# YuanziSTM32.net
KiCad netlist of a schematic drawn in Altium Designer
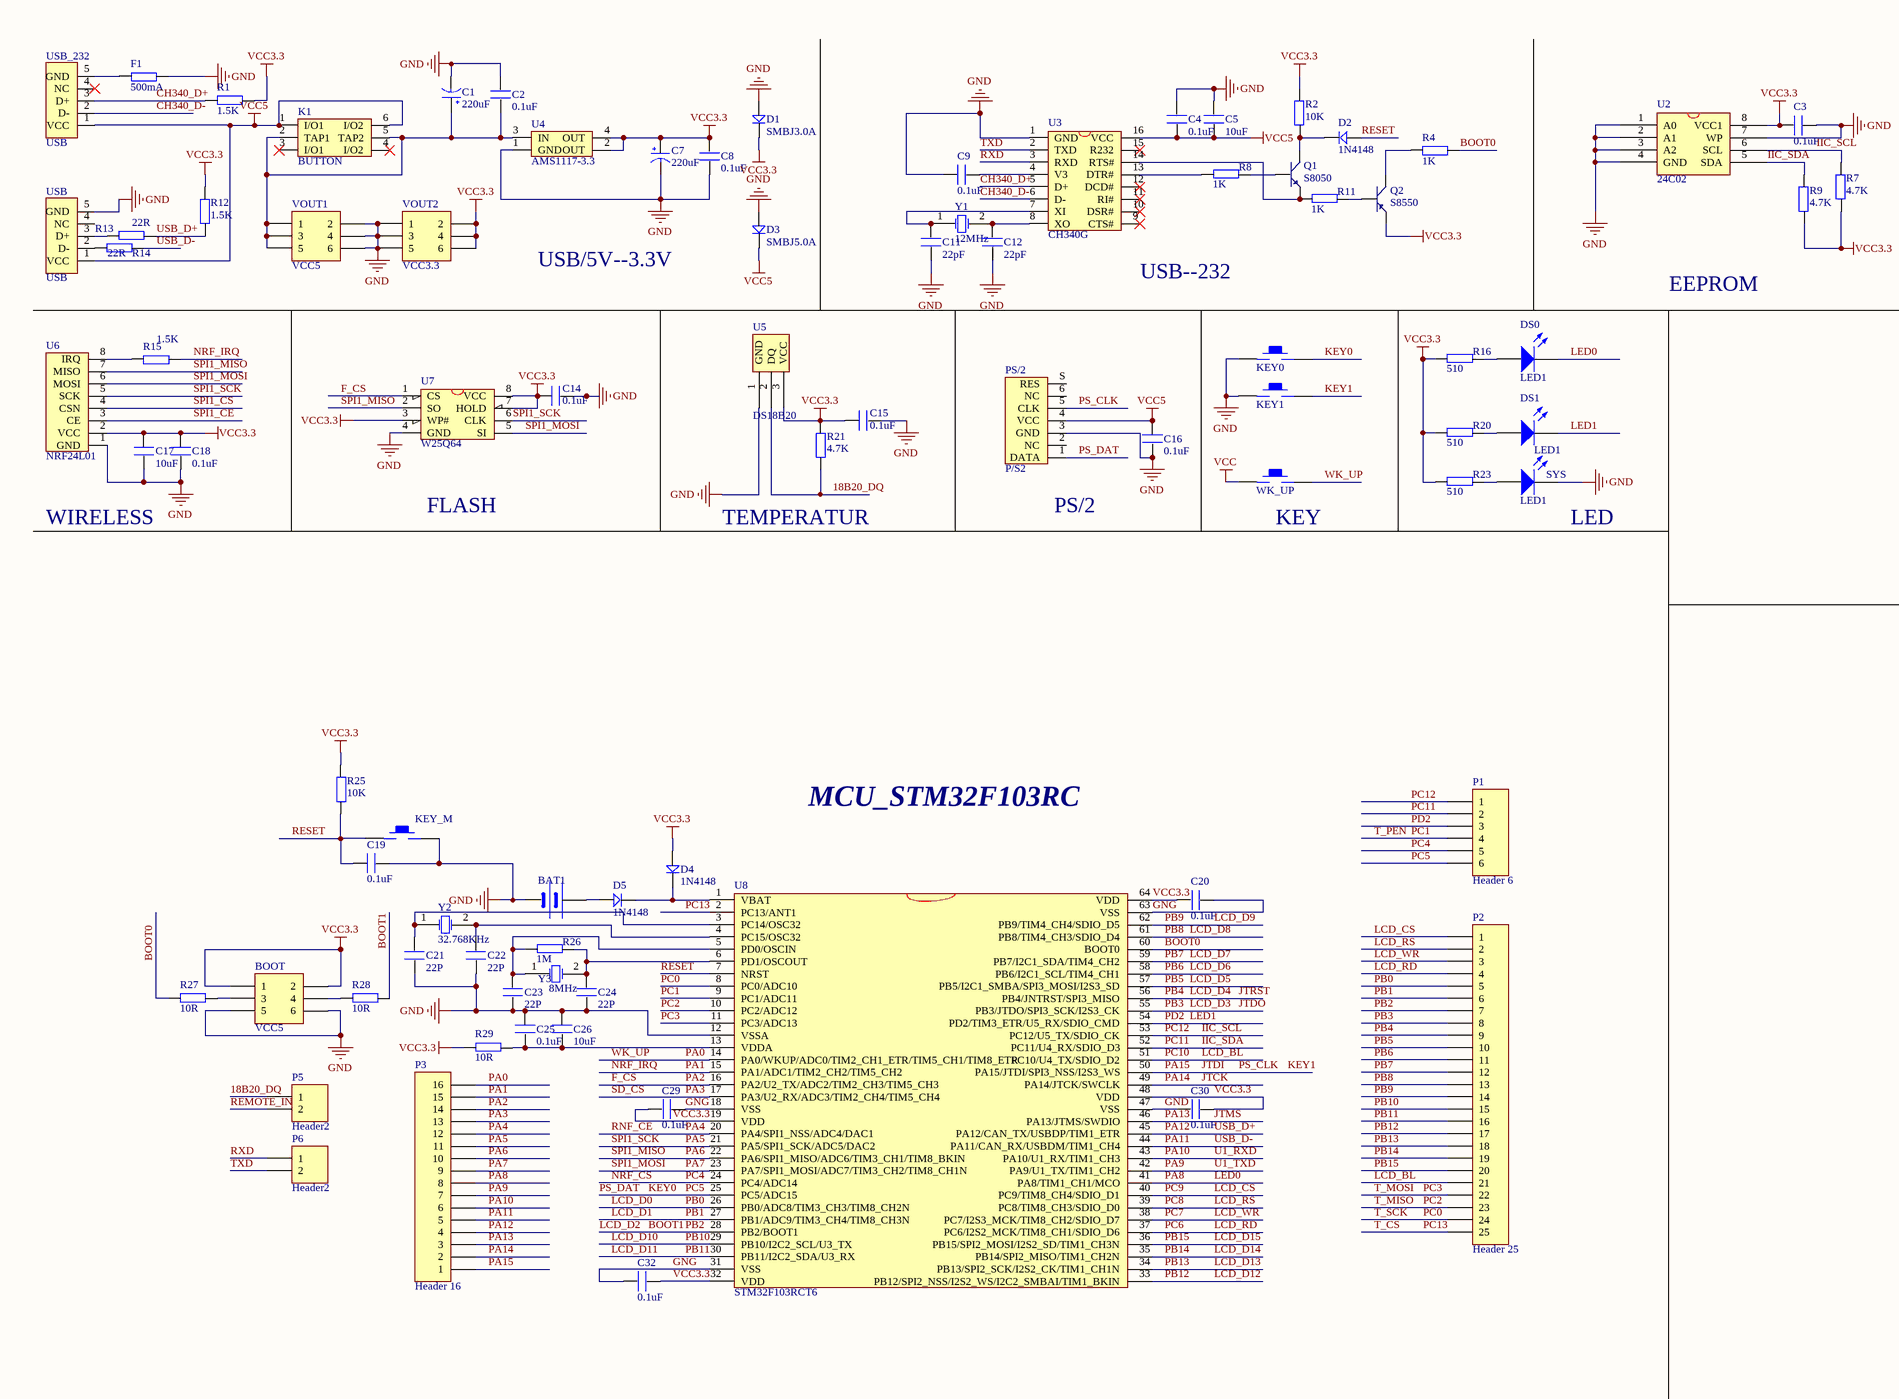
[diagram p0: YuanziSTM32.SchDoc, left]
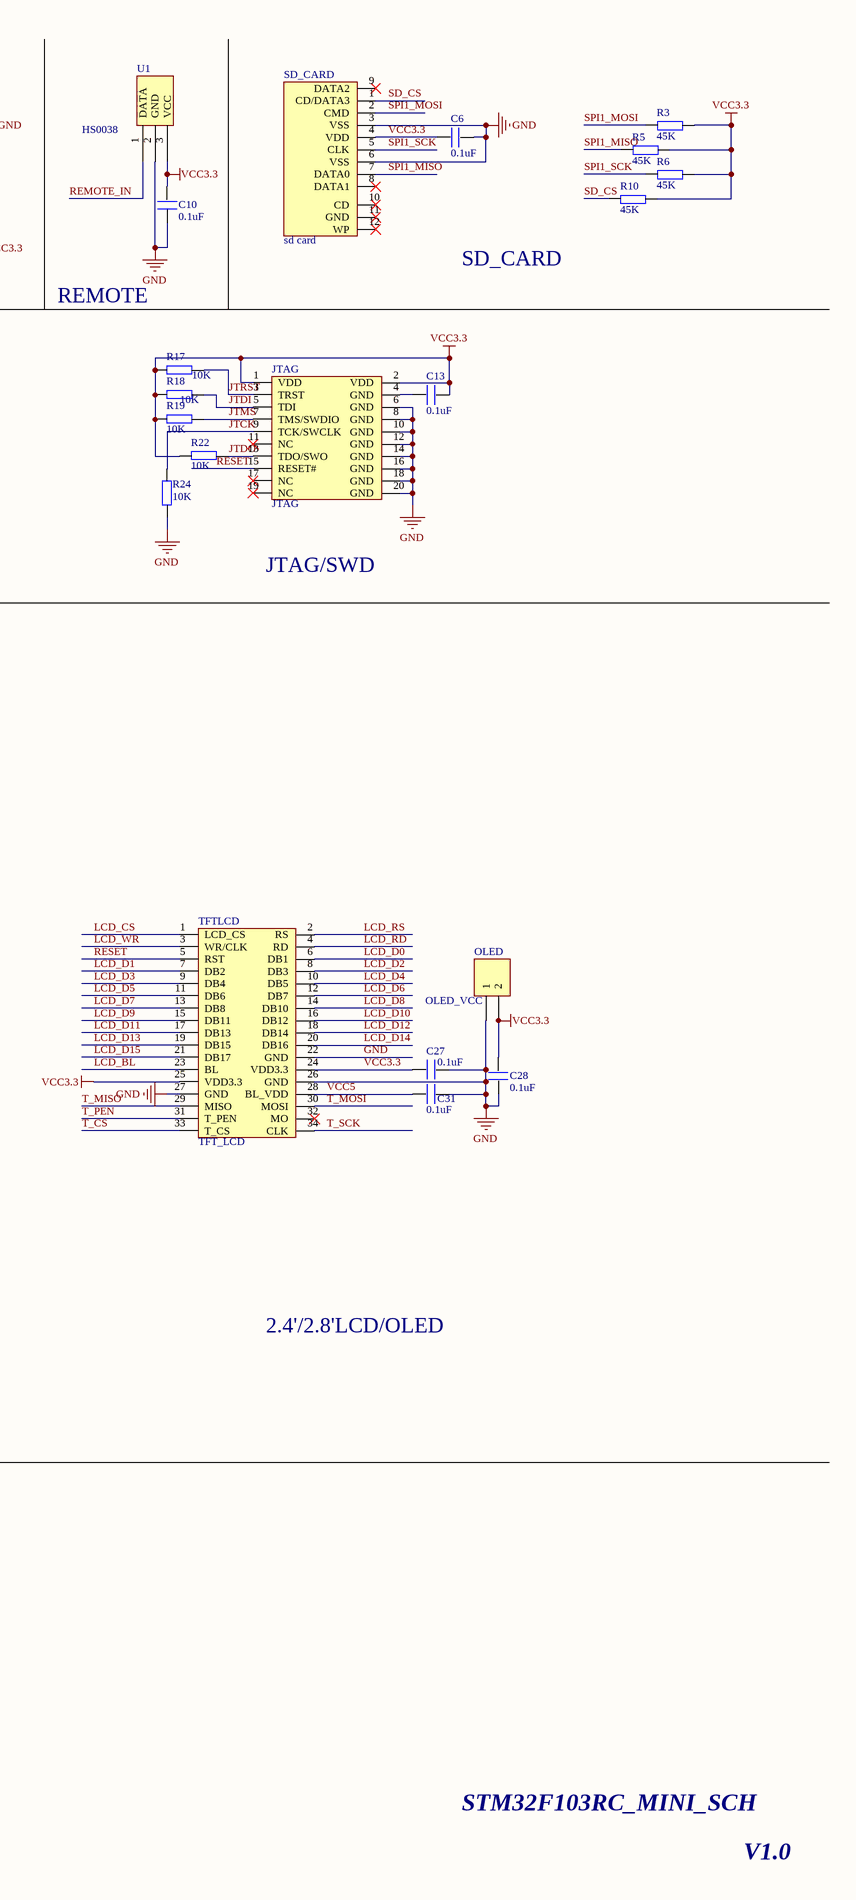
[diagram p1: YuanziSTM32.SchDoc, right]

(export (version "E")
  (design (tool "Eeschema 10.0.6"))
  (components
    (comp (ref "BAT1") (value "BATT") (footprint "BATTERY-CELL") (libsource (lib "CORE") (part "BAT")))
    (comp (ref "BOOT")
      (value "VCC5")
      (footprint "HDR2X3")
      (description "Header, 3-Pin, Dual row")
      (fields (field (name "PUBLISHER") "Altium Limited"))
      (libsource (lib "CORE") (part "Header 3X2"))
    )
    (comp (ref "C1") (value "220uF") (footprint "CC6.56.5") (libsource (lib "CORE") (part "CAP")))
    (comp (ref "C2") (value "0.1uF") (footprint "C0603") (libsource (lib "CORE") (part "C")))
    (comp (ref "C3") (value "0.1uF") (footprint "C0603") (libsource (lib "CORE") (part "C")))
    (comp (ref "C4") (value "0.1uF") (footprint "C0603") (libsource (lib "CORE") (part "C")))
    (comp (ref "C5") (value "10uF") (footprint "C0603") (libsource (lib "CORE") (part "C")))
    (comp (ref "C6") (value "0.1uF") (footprint "C0603") (libsource (lib "CORE") (part "C")))
    (comp (ref "C7") (value "220uF") (footprint "CC6.56.5") (libsource (lib "") (part "CAP_1")))
    (comp (ref "C8") (value "0.1uF") (footprint "C0603") (libsource (lib "CORE") (part "C")))
    (comp (ref "C9") (value "0.1uF") (footprint "C0603") (libsource (lib "CORE") (part "C")))
    (comp (ref "C10") (value "0.1uF") (footprint "C0603") (libsource (lib "CORE") (part "C")))
    (comp (ref "C11") (value "22pF") (footprint "C0603") (libsource (lib "CORE") (part "C")))
    (comp (ref "C12") (value "22pF") (footprint "C0603") (libsource (lib "CORE") (part "C")))
    (comp (ref "C13") (value "0.1uF") (footprint "C0603") (libsource (lib "CORE") (part "C")))
    (comp (ref "C14") (value "0.1uF") (footprint "C0603") (libsource (lib "CORE") (part "C")))
    (comp (ref "C15") (value "0.1uF") (footprint "C0603") (libsource (lib "CORE") (part "C")))
    (comp (ref "C16") (value "0.1uF") (footprint "C0603") (libsource (lib "CORE") (part "C")))
    (comp (ref "C17") (value "10uF") (footprint "C0603") (libsource (lib "CORE") (part "C")))
    (comp (ref "C18") (value "0.1uF") (footprint "C0603") (libsource (lib "CORE") (part "C")))
    (comp (ref "C19") (value "0.1uF") (footprint "C0603") (libsource (lib "CORE") (part "C")))
    (comp (ref "C20") (value "0.1uF") (footprint "C0603") (libsource (lib "CORE") (part "C")))
    (comp (ref "C21") (value "22P") (footprint "C0603") (libsource (lib "CORE") (part "C")))
    (comp (ref "C22") (value "22P") (footprint "C0603") (libsource (lib "CORE") (part "C")))
    (comp (ref "C23") (value "22P") (footprint "C0603") (libsource (lib "CORE") (part "C")))
    (comp (ref "C24") (value "22P") (footprint "C0603") (libsource (lib "CORE") (part "C")))
    (comp (ref "C25") (value "0.1uF") (footprint "C0603") (libsource (lib "CORE") (part "C")))
    (comp (ref "C26") (value "10uF") (footprint "C0603") (libsource (lib "CORE") (part "C")))
    (comp (ref "C27") (value "0.1uF") (footprint "C0603") (libsource (lib "CORE") (part "C")))
    (comp (ref "C28") (value "0.1uF") (footprint "C0603") (libsource (lib "CORE") (part "C")))
    (comp (ref "C29") (value "0.1uF") (footprint "C0603") (libsource (lib "CORE") (part "C")))
    (comp (ref "C30") (value "0.1uF") (footprint "C0603") (libsource (lib "CORE") (part "C")))
    (comp (ref "C31") (value "0.1uF") (footprint "C0603") (libsource (lib "CORE") (part "C")))
    (comp (ref "C32") (value "0.1uF") (footprint "C0603") (libsource (lib "CORE") (part "C")))
    (comp (ref "D1")
      (value "SMBJ3.0A")
      (footprint "DIODE_SOP")
      (description "1N4148")
      (libsource (lib "CORE") (part "D"))
    )
    (comp (ref "D2") (value "1N4148") (footprint "DIODE_SOP") (libsource (lib "CORE") (part "D")))
    (comp (ref "D3")
      (value "SMBJ5.0A")
      (footprint "DIODE_SOP")
      (description "1N4148")
      (libsource (lib "CORE") (part "D"))
    )
    (comp (ref "D4") (value "1N4148") (footprint "D0805") (libsource (lib "CORE") (part "D")))
    (comp (ref "D5") (value "1N4148") (footprint "D0805") (libsource (lib "CORE") (part "D")))
    (comp (ref "DS0")
      (value "LED1")
      (footprint "SMDLED")
      (description "Typical RED, GREEN, YELLOW, AMBER GaAs LED")
      (fields (field (name "PUBLISHER") "Altium Limited"))
      (libsource (lib "CORE") (part "LED2"))
    )
    (comp (ref "DS1")
      (value "LED1")
      (footprint "SMDLED")
      (description "Typical RED, GREEN, YELLOW, AMBER GaAs LED")
      (fields (field (name "PUBLISHER") "Altium Limited"))
      (libsource (lib "CORE") (part "LED2"))
    )
    (comp (ref "F1") (value "500mA") (footprint "0603P") (libsource (lib "CORE") (part "R")))
    (comp (ref "JTAG") (value "JTAG") (footprint "JTAG_20") (libsource (lib "CORE") (part "JTAG")))
    (comp (ref "K1") (value "BUTTON") (footprint "BTN8.5*8.5") (libsource (lib "CORE") (part "BUTTON")))
    (comp (ref "KEY0") (value "KEY_M") (footprint "SW-4PIN-DIP") (libsource (lib "CORE") (part "KEY_M")))
    (comp (ref "KEY1") (value "KEY_M") (footprint "SW-4PIN-DIP") (libsource (lib "CORE") (part "KEY_M")))
    (comp (ref "KEY_M") (value "KEY_M") (footprint "SW-4PIN-DIP") (libsource (lib "CORE") (part "KEY_M")))
    (comp (ref "OLED")
      (value "OLED_VCC")
      (footprint "HDR1X2")
      (description "Header, 2-Pin")
      (fields (field (name "PUBLISHER") "Altium Limited"))
      (libsource (lib "") (part "Header 2_1"))
    )
    (comp (ref "P1")
      (value "Header 6")
      (footprint "HDR1X6")
      (description "Header, 6-Pin")
      (fields (field (name "PUBLISHER") "Altium Limited"))
      (libsource (lib "CORE") (part "Header 6"))
    )
    (comp (ref "P2")
      (value "Header 25")
      (footprint "HDR1X25")
      (description "Header, 25-Pin")
      (fields (field (name "PUBLISHER") "Altium Limited"))
      (libsource (lib "CORE") (part "Header 25"))
    )
    (comp (ref "P3")
      (value "Header 16")
      (footprint "HDR1X16")
      (description "Header, 16-Pin")
      (fields (field (name "PUBLISHER") "Altium Limited"))
      (libsource (lib "CORE") (part "Header 16"))
    )
    (comp (ref "P5")
      (value "Header2")
      (footprint "HDR1X2")
      (description "Header, 2-Pin")
      (fields (field (name "PUBLISHER") "Altium Limited"))
      (libsource (lib "CORE") (part "Header 2"))
    )
    (comp (ref "P6")
      (value "Header2")
      (footprint "HDR1X2")
      (description "Header, 2-Pin")
      (fields (field (name "PUBLISHER") "Altium Limited"))
      (libsource (lib "CORE") (part "Header 2"))
    )
    (comp (ref "PS/2") (value "P/S2") (footprint "PS2-6PIN") (libsource (lib "CORE") (part "P/S2")))
    (comp (ref "Q1")
      (value "S8050")
      (footprint "SOT-23R")
      (description "8050/BCW846/BCW847")
      (libsource (lib "CORE") (part "NPN"))
    )
    (comp (ref "Q2")
      (value "S8550")
      (footprint "SOT-23R")
      (description "8550/BCW68")
      (libsource (lib "CORE") (part "PNP"))
    )
    (comp (ref "R1") (value "1.5K") (footprint "R0603") (libsource (lib "CORE") (part "R")))
    (comp (ref "R2") (value "10K") (footprint "R0603") (libsource (lib "CORE") (part "R")))
    (comp (ref "R3") (value "45K") (footprint "R0603") (libsource (lib "CORE") (part "R")))
    (comp (ref "R4") (value "1K") (footprint "R0603") (libsource (lib "CORE") (part "R")))
    (comp (ref "R5") (value "45K") (footprint "R0603") (libsource (lib "CORE") (part "R")))
    (comp (ref "R6") (value "45K") (footprint "R0603") (libsource (lib "CORE") (part "R")))
    (comp (ref "R7") (value "4.7K") (footprint "R0603") (libsource (lib "CORE") (part "R")))
    (comp (ref "R8") (value "1K") (footprint "R0603") (libsource (lib "CORE") (part "R")))
    (comp (ref "R9") (value "4.7K") (footprint "R0603") (libsource (lib "CORE") (part "R")))
    (comp (ref "R10") (value "45K") (footprint "R0603") (libsource (lib "CORE") (part "R")))
    (comp (ref "R11") (value "1K") (footprint "R0603") (libsource (lib "CORE") (part "R")))
    (comp (ref "R12") (value "1.5K") (footprint "R0603") (libsource (lib "CORE") (part "R")))
    (comp (ref "R13") (value "22R") (footprint "R0603") (libsource (lib "CORE") (part "R")))
    (comp (ref "R14") (value "22R") (footprint "R0603") (libsource (lib "CORE") (part "R")))
    (comp (ref "R15") (value "1.5K") (footprint "R0603") (libsource (lib "CORE") (part "R")))
    (comp (ref "R16") (value "510") (footprint "R0603") (libsource (lib "CORE") (part "R")))
    (comp (ref "R17") (value "10K") (footprint "R0603") (libsource (lib "CORE") (part "R")))
    (comp (ref "R18") (value "10K") (footprint "R0603") (libsource (lib "CORE") (part "R")))
    (comp (ref "R19") (value "10K") (footprint "R0603") (libsource (lib "CORE") (part "R")))
    (comp (ref "R20") (value "510") (footprint "R0603") (libsource (lib "CORE") (part "R")))
    (comp (ref "R21") (value "4.7K") (footprint "R0603") (libsource (lib "CORE") (part "R")))
    (comp (ref "R22") (value "10K") (footprint "R0603") (libsource (lib "CORE") (part "R")))
    (comp (ref "R23") (value "510") (footprint "R0603") (libsource (lib "CORE") (part "R")))
    (comp (ref "R24") (value "10K") (footprint "R0603") (libsource (lib "CORE") (part "R")))
    (comp (ref "R25") (value "10K") (footprint "R0603") (libsource (lib "CORE") (part "R")))
    (comp (ref "R26") (value "1M") (footprint "R0603") (libsource (lib "CORE") (part "R")))
    (comp (ref "R27") (value "10R") (footprint "R0603") (libsource (lib "CORE") (part "R")))
    (comp (ref "R28") (value "10R") (footprint "R0603") (libsource (lib "CORE") (part "R")))
    (comp (ref "R29") (value "10R") (footprint "R0603") (libsource (lib "CORE") (part "R")))
    (comp (ref "SD_CARD") (value "sd card") (footprint "SDCARD_L") (libsource (lib "CORE") (part "sd card")))
    (comp (ref "SYS")
      (value "LED1")
      (footprint "SMDLED")
      (description "Typical RED, GREEN, YELLOW, AMBER GaAs LED")
      (fields (field (name "PUBLISHER") "Altium Limited"))
      (libsource (lib "CORE") (part "LED2"))
    )
    (comp (ref "TFTLCD") (value "TFT_LCD") (footprint "DB2*17") (libsource (lib "CORE") (part "TFT_LCD")))
    (comp (ref "U1") (value "HS0038") (footprint "HS0038") (libsource (lib "CORE") (part "HS0038")))
    (comp (ref "U2") (value "24C02") (footprint "SOP-8") (libsource (lib "CORE") (part "24C256")))
    (comp (ref "U3")
      (value "CH340G")
      (footprint "SOIC16")
      (description "USB2UART")
      (libsource (lib "CORE") (part "CH340G"))
    )
    (comp (ref "U4") (value "AMS1117-3.3") (footprint "AMS1117") (libsource (lib "CORE") (part "AMS1117")))
    (comp (ref "U5") (value "DS18B20") (footprint "DS18B20") (libsource (lib "CORE") (part "DS18B20")))
    (comp (ref "U6") (value "NRF24L01") (footprint "NRF24L01") (libsource (lib "CORE") (part "NRF24L01")))
    (comp (ref "U7")
      (value "W25Q64")
      (footprint "SOP-8")
      (description "W25X16;SST25VF016;MX25L1605")
      (libsource (lib "CORE") (part "W25X16"))
    )
    (comp (ref "U8")
      (value "STM32F103RCT6")
      (footprint "LQFP64")
      (libsource (lib "CORE") (part "STM32F103RDT6"))
    )
    (comp (ref "USB") (value "USB") (footprint "USB/SM0.8-6H5") (libsource (lib "CORE") (part "USB5")))
    (comp (ref "USB_232") (value "USB") (footprint "USB/SM0.8-6H5") (libsource (lib "CORE") (part "USB5")))
    (comp (ref "VOUT1")
      (value "VCC5")
      (footprint "HDR2X3")
      (description "Header, 3-Pin, Dual row")
      (fields (field (name "PUBLISHER") "Altium Limited"))
      (libsource (lib "CORE") (part "Header 3X2"))
    )
    (comp (ref "VOUT2")
      (value "VCC3.3")
      (footprint "HDR2X3")
      (description "Header, 3-Pin, Dual row")
      (fields (field (name "PUBLISHER") "Altium Limited"))
      (libsource (lib "CORE") (part "Header 3X2"))
    )
    (comp (ref "WK_UP") (value "KEY_M") (footprint "SW-4PIN-DIP") (libsource (lib "CORE") (part "KEY_M")))
    (comp (ref "Y1")
      (value "12MHz")
      (footprint "XTAL")
      (description "Crystal Oscillator")
      (fields (field (name "PUBLISHER") "Altium Limited"))
      (libsource (lib "CORE") (part "XTAL"))
    )
    (comp (ref "Y2")
      (value "32.768KHz")
      (footprint "X_32.768KHZ - duplicate")
      (description "Crystal Oscillator")
      (fields (field (name "PUBLISHER") "Altium Limited"))
      (libsource (lib "CORE") (part "XTAL"))
    )
    (comp (ref "Y3")
      (value "8MHz")
      (footprint "XTAL")
      (description "Crystal Oscillator")
      (fields (field (name "PUBLISHER") "Altium Limited"))
      (libsource (lib "CORE") (part "XTAL"))
    )
  )
  (nets
    (net (code "1") (name "/18B20_DQ") (class "Default")
      (node (ref "P5") (pin "1") (pinfunction "1_1") (pintype "passive"))
      (node (ref "R21") (pin "1") (pintype "passive"))
      (node (ref "U5") (pin "2") (pinfunction "DQ_2") (pintype "passive"))
    )
    (net (code "2") (name "/BOOT0") (class "Default")
      (node (ref "R27") (pin "2") (pintype "passive"))
      (node (ref "R4") (pin "2") (pintype "passive"))
      (node (ref "U8") (pin "60") (pinfunction "BOOT0_60") (pintype "passive"))
    )
    (net (code "3") (name "/BOOT1") (class "Default")
      (node (ref "P2") (pin "7") (pinfunction "7_7") (pintype "passive"))
      (node (ref "R28") (pin "1") (pintype "passive"))
      (node (ref "TFTLCD") (pin "8") (pinfunction "DB3_8") (pintype "passive"))
      (node (ref "U8") (pin "28") (pinfunction "PB2/BOOT1_28") (pintype "passive"))
    )
    (net (code "4") (name "/CH340_D+") (class "Default")
      (node (ref "R1") (pin "2") (pintype "passive"))
      (node (ref "U3") (pin "5") (pinfunction "D+_5") (pintype "passive"))
      (node (ref "USB") (pin "3") (pinfunction "D+_3") (pintype "passive"))
    )
    (net (code "5") (name "/CH340_D-") (class "Default")
      (node (ref "U3") (pin "6") (pinfunction "D-_6") (pintype "passive"))
      (node (ref "USB") (pin "2") (pinfunction "D-_2") (pintype "passive"))
    )
    (net (code "6") (name "/F_CS") (class "Default")
      (node (ref "P3") (pin "14") (pinfunction "14_14") (pintype "passive"))
      (node (ref "U7") (pin "1") (pinfunction "CS_1") (pintype "passive"))
      (node (ref "U8") (pin "16") (pinfunction "PA2/U2_TX/ADC2/TIM2_CH3/TIM5_CH3_16") (pintype "passive"))
    )
    (net (code "7") (name "/GNG") (class "Default")
      (node (ref "C20") (pin "1") (pintype "passive"))
      (node (ref "C29") (pin "1") (pintype "passive"))
      (node (ref "C32") (pin "2") (pintype "passive"))
      (node (ref "U8") (pin "18") (pinfunction "VSS_18") (pintype "passive"))
      (node (ref "U8") (pin "31") (pinfunction "VSS_31") (pintype "passive"))
      (node (ref "U8") (pin "63") (pinfunction "VSS_63") (pintype "passive"))
    )
    (net (code "8") (name "/IIC_SCL") (class "Default")
      (node (ref "P1") (pin "1") (pinfunction "1_1") (pintype "passive"))
      (node (ref "R7") (pin "1") (pintype "passive"))
      (node (ref "U2") (pin "6") (pinfunction "SCL_6") (pintype "passive"))
      (node (ref "U8") (pin "53") (pinfunction "PC12/U5_TX/SDIO_CK_53") (pintype "passive"))
    )
    (net (code "9") (name "/IIC_SDA") (class "Default")
      (node (ref "P1") (pin "2") (pinfunction "2_2") (pintype "passive"))
      (node (ref "R9") (pin "1") (pintype "passive"))
      (node (ref "U2") (pin "5") (pinfunction "SDA_5") (pintype "passive"))
      (node (ref "U8") (pin "52") (pinfunction "PC11/U4_RX/SDIO_D3_52") (pintype "passive"))
    )
    (net (code "10") (name "/JTCK") (class "Default")
      (node (ref "JTAG") (pin "9") (pinfunction "TCK/SWCLK_9") (pintype "passive"))
      (node (ref "P3") (pin "2") (pinfunction "2_2") (pintype "passive"))
      (node (ref "R24") (pin "1") (pintype "passive"))
      (node (ref "U8") (pin "49") (pinfunction "PA14/JTCK/SWCLK_49") (pintype "passive"))
    )
    (net (code "11") (name "/JTDI") (class "Default")
      (node (ref "JTAG") (pin "5") (pinfunction "TDI_5") (pintype "passive"))
      (node (ref "KEY1") (pin "2") (pinfunction "2_2") (pintype "passive"))
      (node (ref "P3") (pin "1") (pinfunction "1_1") (pintype "passive"))
      (node (ref "PS/2") (pin "5") (pinfunction "CLK_5") (pintype "passive"))
      (node (ref "R18") (pin "1") (pintype "passive"))
      (node (ref "U8") (pin "50") (pinfunction "PA15/JTDI/SPI3_NSS/I2S3_WS_50") (pintype "passive"))
    )
    (net (code "12") (name "/JTDO") (class "Default")
      (node (ref "JTAG") (pin "13") (pinfunction "TDO/SWO_13") (pintype "passive"))
      (node (ref "P2") (pin "8") (pinfunction "8_8") (pintype "passive"))
      (node (ref "R22") (pin "1") (pintype "passive"))
      (node (ref "TFTLCD") (pin "9") (pinfunction "DB4_9") (pintype "passive"))
      (node (ref "U8") (pin "55") (pinfunction "PB3/JTDO/SPI3_SCK/I2S3_CK_55") (pintype "passive"))
    )
    (net (code "13") (name "/JTMS") (class "Default")
      (node (ref "JTAG") (pin "7") (pinfunction "TMS/SWDIO_7") (pintype "passive"))
      (node (ref "P3") (pin "3") (pinfunction "3_3") (pintype "passive"))
      (node (ref "R19") (pin "1") (pintype "passive"))
      (node (ref "U8") (pin "46") (pinfunction "PA13/JTMS/SWDIO_46") (pintype "passive"))
    )
    (net (code "14") (name "/JTRST") (class "Default")
      (node (ref "JTAG") (pin "3") (pinfunction "TRST_3") (pintype "passive"))
      (node (ref "P2") (pin "9") (pinfunction "9_9") (pintype "passive"))
      (node (ref "R17") (pin "1") (pintype "passive"))
      (node (ref "TFTLCD") (pin "10") (pinfunction "DB5_10") (pintype "passive"))
      (node (ref "U8") (pin "56") (pinfunction "PB4/JNTRST/SPI3_MISO_56") (pintype "passive"))
    )
    (net (code "15") (name "/KEY0") (class "Default")
      (node (ref "KEY0") (pin "2") (pinfunction "2_2") (pintype "passive"))
      (node (ref "P1") (pin "6") (pinfunction "6_6") (pintype "passive"))
      (node (ref "PS/2") (pin "1") (pinfunction "DATA_1") (pintype "passive"))
      (node (ref "U8") (pin "25") (pinfunction "PC5/ADC15_25") (pintype "passive"))
    )
    (net (code "16") (name "/LCD_BL") (class "Default")
      (node (ref "P2") (pin "21") (pinfunction "21_21") (pintype "passive"))
      (node (ref "TFTLCD") (pin "23") (pinfunction "BL_23") (pintype "passive"))
      (node (ref "U8") (pin "51") (pinfunction "PC10/U4_TX/SDIO_D2_51") (pintype "passive"))
    )
    (net (code "17") (name "/LCD_CS") (class "Default")
      (node (ref "P2") (pin "1") (pinfunction "1_1") (pintype "passive"))
      (node (ref "TFTLCD") (pin "1") (pinfunction "LCD_CS_1") (pintype "passive"))
      (node (ref "U8") (pin "40") (pinfunction "PC9/TIM8_CH4/SDIO_D1_40") (pintype "passive"))
    )
    (net (code "18") (name "/LCD_D0") (class "Default")
      (node (ref "P2") (pin "5") (pinfunction "5_5") (pintype "passive"))
      (node (ref "TFTLCD") (pin "6") (pinfunction "DB1_6") (pintype "passive"))
      (node (ref "U8") (pin "26") (pinfunction "PB0/ADC8/TIM3_CH3/TIM8_CH2N_26") (pintype "passive"))
    )
    (net (code "19") (name "/LCD_D1") (class "Default")
      (node (ref "P2") (pin "6") (pinfunction "6_6") (pintype "passive"))
      (node (ref "TFTLCD") (pin "7") (pinfunction "DB2_7") (pintype "passive"))
      (node (ref "U8") (pin "27") (pinfunction "PB1/ADC9/TIM3_CH4/TIM8_CH3N_27") (pintype "passive"))
    )
    (net (code "20") (name "/LCD_D5") (class "Default")
      (node (ref "P2") (pin "10") (pinfunction "10_10") (pintype "passive"))
      (node (ref "TFTLCD") (pin "11") (pinfunction "DB6_11") (pintype "passive"))
      (node (ref "U8") (pin "57") (pinfunction "PB5/I2C1_SMBA/SPI3_MOSI/I2S3_SD_57") (pintype "passive"))
    )
    (net (code "21") (name "/LCD_D6") (class "Default")
      (node (ref "P2") (pin "11") (pinfunction "11_11") (pintype "passive"))
      (node (ref "TFTLCD") (pin "12") (pinfunction "DB7_12") (pintype "passive"))
      (node (ref "U8") (pin "58") (pinfunction "PB6/I2C1_SCL/TIM4_CH1_58") (pintype "passive"))
    )
    (net (code "22") (name "/LCD_D7") (class "Default")
      (node (ref "P2") (pin "12") (pinfunction "12_12") (pintype "passive"))
      (node (ref "TFTLCD") (pin "13") (pinfunction "DB8_13") (pintype "passive"))
      (node (ref "U8") (pin "59") (pinfunction "PB7/I2C1_SDA/TIM4_CH2_59") (pintype "passive"))
    )
    (net (code "23") (name "/LCD_D8") (class "Default")
      (node (ref "P2") (pin "13") (pinfunction "13_13") (pintype "passive"))
      (node (ref "TFTLCD") (pin "14") (pinfunction "DB10_14") (pintype "passive"))
      (node (ref "U8") (pin "61") (pinfunction "PB8/TIM4_CH3/SDIO_D4_61") (pintype "passive"))
    )
    (net (code "24") (name "/LCD_D9") (class "Default")
      (node (ref "P2") (pin "14") (pinfunction "14_14") (pintype "passive"))
      (node (ref "TFTLCD") (pin "15") (pinfunction "DB11_15") (pintype "passive"))
      (node (ref "U8") (pin "62") (pinfunction "PB9/TIM4_CH4/SDIO_D5_62") (pintype "passive"))
    )
    (net (code "25") (name "/LCD_D10") (class "Default")
      (node (ref "P2") (pin "15") (pinfunction "15_15") (pintype "passive"))
      (node (ref "TFTLCD") (pin "16") (pinfunction "DB12_16") (pintype "passive"))
      (node (ref "U8") (pin "29") (pinfunction "PB10/I2C2_SCL/U3_TX_29") (pintype "passive"))
    )
    (net (code "26") (name "/LCD_D11") (class "Default")
      (node (ref "P2") (pin "16") (pinfunction "16_16") (pintype "passive"))
      (node (ref "TFTLCD") (pin "17") (pinfunction "DB13_17") (pintype "passive"))
      (node (ref "U8") (pin "30") (pinfunction "PB11/I2C2_SDA/U3_RX_30") (pintype "passive"))
    )
    (net (code "27") (name "/LCD_D12") (class "Default")
      (node (ref "P2") (pin "17") (pinfunction "17_17") (pintype "passive"))
      (node (ref "TFTLCD") (pin "18") (pinfunction "DB14_18") (pintype "passive"))
      (node (ref "U8") (pin "33") (pinfunction "PB12/SPI2_NSS/I2S2_WS/I2C2_SMBAI/TIM1_BKIN_33") (pintype "passive"))
    )
    (net (code "28") (name "/LCD_D13") (class "Default")
      (node (ref "P2") (pin "18") (pinfunction "18_18") (pintype "passive"))
      (node (ref "TFTLCD") (pin "19") (pinfunction "DB15_19") (pintype "passive"))
      (node (ref "U8") (pin "34") (pinfunction "PB13/SPI2_SCK/I2S2_CK/TIM1_CH1N_34") (pintype "passive"))
    )
    (net (code "29") (name "/LCD_D14") (class "Default")
      (node (ref "P2") (pin "19") (pinfunction "19_19") (pintype "passive"))
      (node (ref "TFTLCD") (pin "20") (pinfunction "DB16_20") (pintype "passive"))
      (node (ref "U8") (pin "35") (pinfunction "PB14/SPI2_MISO/TIM1_CH2N_35") (pintype "passive"))
    )
    (net (code "30") (name "/LCD_D15") (class "Default")
      (node (ref "P2") (pin "20") (pinfunction "20_20") (pintype "passive"))
      (node (ref "TFTLCD") (pin "21") (pinfunction "DB17_21") (pintype "passive"))
      (node (ref "U8") (pin "36") (pinfunction "PB15/SPI2_MOSI/I2S2_SD/TIM1_CH3N_36") (pintype "passive"))
    )
    (net (code "31") (name "/LCD_RD") (class "Default")
      (node (ref "P2") (pin "4") (pinfunction "4_4") (pintype "passive"))
      (node (ref "TFTLCD") (pin "4") (pinfunction "RD_4") (pintype "passive"))
      (node (ref "U8") (pin "37") (pinfunction "PC6/I2S2_MCK/TIM8_CH1/SDIO_D6_37") (pintype "passive"))
    )
    (net (code "32") (name "/LCD_RS") (class "Default")
      (node (ref "P2") (pin "2") (pinfunction "2_2") (pintype "passive"))
      (node (ref "TFTLCD") (pin "2") (pinfunction "RS_2") (pintype "passive"))
      (node (ref "U8") (pin "39") (pinfunction "PC8/TIM8_CH3/SDIO_D0_39") (pintype "passive"))
    )
    (net (code "33") (name "/LCD_WR") (class "Default")
      (node (ref "P2") (pin "3") (pinfunction "3_3") (pintype "passive"))
      (node (ref "TFTLCD") (pin "3") (pinfunction "WR/CLK_3") (pintype "passive"))
      (node (ref "U8") (pin "38") (pinfunction "PC7/I2S3_MCK/TIM8_CH2/SDIO_D7_38") (pintype "passive"))
    )
    (net (code "34") (name "/LED0") (class "Default")
      (node (ref "DS0") (pin "2") (pinfunction "K_2") (pintype "passive"))
      (node (ref "P3") (pin "8") (pinfunction "8_8") (pintype "passive"))
      (node (ref "U8") (pin "41") (pinfunction "PA8/TIM1_CH1/MCO_41") (pintype "passive"))
    )
    (net (code "35") (name "/LED1") (class "Default")
      (node (ref "DS1") (pin "2") (pinfunction "K_2") (pintype "passive"))
      (node (ref "P1") (pin "3") (pinfunction "3_3") (pintype "passive"))
      (node (ref "U8") (pin "54") (pinfunction "PD2/TIM3_ETR/U5_RX/SDIO_CMD_54") (pintype "passive"))
    )
    (net (code "36") (name "/NRF_CS") (class "Default")
      (node (ref "P1") (pin "5") (pinfunction "5_5") (pintype "passive"))
      (node (ref "U8") (pin "24") (pinfunction "PC4/ADC14_24") (pintype "passive"))
    )
    (net (code "37") (name "/NRF_IRQ") (class "Default")
      (node (ref "P3") (pin "15") (pinfunction "15_15") (pintype "passive"))
      (node (ref "R15") (pin "2") (pintype "passive"))
      (node (ref "U8") (pin "15") (pinfunction "PA1/ADC1/TIM2_CH2/TIM5_CH2_15") (pintype "passive"))
    )
    (net (code "38") (name "/PA0") (class "Default")
      (node (ref "P3") (pin "16") (pinfunction "16_16") (pintype "passive"))
      (node (ref "U8") (pin "14") (pinfunction "PA0/WKUP/ADC0/TIM2_CH1_ETR/TIM5_CH1/TIM8_ETR_14") (pintype "passive"))
      (node (ref "WK_UP") (pin "2") (pinfunction "2_2") (pintype "passive"))
    )
    (net (code "39") (name "/PA3") (class "Default")
      (node (ref "P3") (pin "13") (pinfunction "13_13") (pintype "passive"))
      (node (ref "R10") (pin "1") (pintype "passive"))
      (node (ref "SD_CARD") (pin "1") (pinfunction "CD/DATA3_1") (pintype "passive"))
      (node (ref "U8") (pin "17") (pinfunction "PA3/U2_RX/ADC3/TIM2_CH4/TIM5_CH4_17") (pintype "passive"))
    )
    (net (code "40") (name "/PA4") (class "Default")
      (node (ref "P3") (pin "12") (pinfunction "12_12") (pintype "passive"))
      (node (ref "U8") (pin "20") (pinfunction "PA4/SPI1_NSS/ADC4/DAC1_20") (pintype "passive"))
    )
    (net (code "41") (name "/PA5") (class "Default")
      (node (ref "P3") (pin "11") (pinfunction "11_11") (pintype "passive"))
      (node (ref "R6") (pin "1") (pintype "passive"))
      (node (ref "SD_CARD") (pin "5") (pinfunction "CLK_5") (pintype "passive"))
      (node (ref "U6") (pin "5") (pinfunction "SCK_5") (pintype "passive"))
      (node (ref "U7") (pin "6") (pinfunction "CLK_6") (pintype "passive"))
      (node (ref "U8") (pin "21") (pinfunction "PA5/SPI1_SCK/ADC5/DAC2_21") (pintype "passive"))
    )
    (net (code "42") (name "/PA6") (class "Default")
      (node (ref "P3") (pin "10") (pinfunction "10_10") (pintype "passive"))
      (node (ref "R5") (pin "1") (pintype "passive"))
      (node (ref "SD_CARD") (pin "7") (pinfunction "DATA0_7") (pintype "passive"))
      (node (ref "U6") (pin "7") (pinfunction "MISO_7") (pintype "passive"))
      (node (ref "U7") (pin "2") (pinfunction "SO_2") (pintype "passive"))
      (node (ref "U8") (pin "22") (pinfunction "PA6/SPI1_MISO/ADC6/TIM3_CH1/TIM8_BKIN_22") (pintype "passive"))
    )
    (net (code "43") (name "/PA7") (class "Default")
      (node (ref "P3") (pin "9") (pinfunction "9_9") (pintype "passive"))
      (node (ref "R3") (pin "1") (pintype "passive"))
      (node (ref "SD_CARD") (pin "2") (pinfunction "CMD_2") (pintype "passive"))
      (node (ref "U6") (pin "6") (pinfunction "MOSI_6") (pintype "passive"))
      (node (ref "U7") (pin "5") (pinfunction "SI_5") (pintype "passive"))
      (node (ref "U8") (pin "23") (pinfunction "PA7/SPI1_MOSI/ADC7/TIM3_CH2/TIM8_CH1N_23") (pintype "passive"))
    )
    (net (code "44") (name "/PA9") (class "Default")
      (node (ref "P3") (pin "7") (pinfunction "7_7") (pintype "passive"))
      (node (ref "U8") (pin "42") (pinfunction "PA9/U1_TX/TIM1_CH2_42") (pintype "passive"))
    )
    (net (code "45") (name "/PA10") (class "Default")
      (node (ref "P3") (pin "6") (pinfunction "6_6") (pintype "passive"))
      (node (ref "U8") (pin "43") (pinfunction "PA10/U1_RX/TIM1_CH3_43") (pintype "passive"))
    )
    (net (code "46") (name "/PA11") (class "Default")
      (node (ref "P3") (pin "5") (pinfunction "5_5") (pintype "passive"))
      (node (ref "R14") (pin "1") (pintype "passive"))
      (node (ref "U8") (pin "44") (pinfunction "PA11/CAN_RX/USBDM/TIM1_CH4_44") (pintype "passive"))
    )
    (net (code "47") (name "/PA12") (class "Default")
      (node (ref "P3") (pin "4") (pinfunction "4_4") (pintype "passive"))
      (node (ref "R12") (pin "2") (pintype "passive"))
      (node (ref "R13") (pin "1") (pintype "passive"))
      (node (ref "U8") (pin "45") (pinfunction "PA12/CAN_TX/USBDP/TIM1_ETR_45") (pintype "passive"))
    )
    (net (code "48") (name "/PC0") (class "Default")
      (node (ref "P2") (pin "24") (pinfunction "24_24") (pintype "passive"))
      (node (ref "TFTLCD") (pin "34") (pinfunction "CLK_34") (pintype "passive"))
      (node (ref "U8") (pin "8") (pinfunction "PC0/ADC10_8") (pintype "passive"))
    )
    (net (code "49") (name "/PC1") (class "Default")
      (node (ref "P1") (pin "4") (pinfunction "4_4") (pintype "passive"))
      (node (ref "TFTLCD") (pin "31") (pinfunction "T_PEN_31") (pintype "passive"))
      (node (ref "U8") (pin "9") (pinfunction "PC1/ADC11_9") (pintype "passive"))
    )
    (net (code "50") (name "/PC2") (class "Default")
      (node (ref "P2") (pin "23") (pinfunction "23_23") (pintype "passive"))
      (node (ref "TFTLCD") (pin "29") (pinfunction "MISO_29") (pintype "passive"))
      (node (ref "U8") (pin "10") (pinfunction "PC2/ADC12_10") (pintype "passive"))
    )
    (net (code "51") (name "/PC3") (class "Default")
      (node (ref "P2") (pin "22") (pinfunction "22_22") (pintype "passive"))
      (node (ref "TFTLCD") (pin "30") (pinfunction "MOSI_30") (pintype "passive"))
      (node (ref "U8") (pin "11") (pinfunction "PC3/ADC13_11") (pintype "passive"))
    )
    (net (code "52") (name "/PC13") (class "Default")
      (node (ref "P2") (pin "25") (pinfunction "25_25") (pintype "passive"))
      (node (ref "TFTLCD") (pin "33") (pinfunction "T_CS_33") (pintype "passive"))
      (node (ref "U8") (pin "2") (pinfunction "PC13/ANT1_2") (pintype "passive"))
    )
    (net (code "53") (name "/REMOTE_IN") (class "Default")
      (node (ref "P5") (pin "2") (pinfunction "2_2") (pintype "passive"))
      (node (ref "U1") (pin "1") (pinfunction "DATA_1") (pintype "passive"))
    )
    (net (code "54") (name "/RESET") (class "Default")
      (node (ref "C19") (pin "1") (pintype "passive"))
      (node (ref "D2") (pin "1") (pintype "passive"))
      (node (ref "JTAG") (pin "15") (pinfunction "RESET#_15") (pintype "passive"))
      (node (ref "KEY_M") (pin "1") (pinfunction "1_1") (pintype "passive"))
      (node (ref "R25") (pin "1") (pintype "passive"))
      (node (ref "TFTLCD") (pin "5") (pinfunction "RST_5") (pintype "passive"))
      (node (ref "U8") (pin "7") (pinfunction "NRST_7") (pintype "passive"))
    )
    (net (code "55") (name "/RXD") (class "Default")
      (node (ref "P6") (pin "1") (pinfunction "1_1") (pintype "passive"))
      (node (ref "U3") (pin "3") (pinfunction "RXD_3") (pintype "passive"))
    )
    (net (code "56") (name "/SPI1_CE") (class "Default")
      (node (ref "U6") (pin "3") (pinfunction "CE_3") (pintype "passive"))
    )
    (net (code "57") (name "/SPI1_CS") (class "Default")
      (node (ref "U6") (pin "4") (pinfunction "CSN_4") (pintype "passive"))
    )
    (net (code "58") (name "/TXD") (class "Default")
      (node (ref "P6") (pin "2") (pinfunction "2_2") (pintype "passive"))
      (node (ref "U3") (pin "2") (pinfunction "TXD_2") (pintype "passive"))
    )
    (net (code "59") (name "GND") (class "Default")
      (node (ref "BAT1") (pin "2") (pinfunction "GND_2") (pintype "passive"))
      (node (ref "BOOT") (pin "5") (pinfunction "5_5") (pintype "passive"))
      (node (ref "BOOT") (pin "6") (pinfunction "6_6") (pintype "passive"))
      (node (ref "C1") (pin "2") (pinfunction "GND_2") (pintype "passive"))
      (node (ref "C10") (pin "2") (pintype "passive"))
      (node (ref "C11") (pin "1") (pintype "passive"))
      (node (ref "C12") (pin "1") (pintype "passive"))
      (node (ref "C14") (pin "2") (pintype "passive"))
      (node (ref "C15") (pin "2") (pintype "passive"))
      (node (ref "C16") (pin "1") (pintype "passive"))
      (node (ref "C17") (pin "1") (pintype "passive"))
      (node (ref "C18") (pin "1") (pintype "passive"))
      (node (ref "C19") (pin "2") (pintype "passive"))
      (node (ref "C2") (pin "2") (pintype "passive"))
      (node (ref "C21") (pin "1") (pintype "passive"))
      (node (ref "C22") (pin "1") (pintype "passive"))
      (node (ref "C23") (pin "1") (pintype "passive"))
      (node (ref "C24") (pin "1") (pintype "passive"))
      (node (ref "C25") (pin "2") (pintype "passive"))
      (node (ref "C26") (pin "2") (pintype "passive"))
      (node (ref "C27") (pin "1") (pintype "passive"))
      (node (ref "C28") (pin "2") (pintype "passive"))
      (node (ref "C3") (pin "1") (pintype "passive"))
      (node (ref "C30") (pin "2") (pintype "passive"))
      (node (ref "C31") (pin "1") (pintype "passive"))
      (node (ref "C4") (pin "2") (pintype "passive"))
      (node (ref "C5") (pin "2") (pintype "passive"))
      (node (ref "C6") (pin "2") (pintype "passive"))
      (node (ref "C7") (pin "2") (pinfunction "GND_2") (pintype "passive"))
      (node (ref "C8") (pin "2") (pintype "passive"))
      (node (ref "C9") (pin "1") (pintype "passive"))
      (node (ref "D1") (pin "1") (pintype "passive"))
      (node (ref "D3") (pin "1") (pintype "passive"))
      (node (ref "F1") (pin "2") (pintype "passive"))
      (node (ref "JTAG") (pin "10") (pinfunction "GND_10") (pintype "passive"))
      (node (ref "JTAG") (pin "12") (pinfunction "GND_12") (pintype "passive"))
      (node (ref "JTAG") (pin "14") (pinfunction "GND_14") (pintype "passive"))
      (node (ref "JTAG") (pin "16") (pinfunction "GND_16") (pintype "passive"))
      (node (ref "JTAG") (pin "18") (pinfunction "GND_18") (pintype "passive"))
      (node (ref "JTAG") (pin "20") (pinfunction "GND_20") (pintype "passive"))
      (node (ref "JTAG") (pin "6") (pinfunction "GND_6") (pintype "passive"))
      (node (ref "JTAG") (pin "8") (pinfunction "GND_8") (pintype "passive"))
      (node (ref "KEY0") (pin "1") (pinfunction "1_1") (pintype "passive"))
      (node (ref "KEY1") (pin "1") (pinfunction "1_1") (pintype "passive"))
      (node (ref "KEY_M") (pin "2") (pinfunction "2_2") (pintype "passive"))
      (node (ref "OLED") (pin "1") (pinfunction "1_1") (pintype "passive"))
      (node (ref "PS/2") (pin "3") (pinfunction "GND_3") (pintype "passive"))
      (node (ref "R24") (pin "2") (pintype "passive"))
      (node (ref "SD_CARD") (pin "3") (pinfunction "VSS_3") (pintype "passive"))
      (node (ref "SD_CARD") (pin "6") (pinfunction "VSS_6") (pintype "passive"))
      (node (ref "SYS") (pin "2") (pinfunction "K_2") (pintype "passive"))
      (node (ref "TFTLCD") (pin "22") (pinfunction "GND_22") (pintype "passive"))
      (node (ref "TFTLCD") (pin "26") (pinfunction "GND_26") (pintype "passive"))
      (node (ref "TFTLCD") (pin "27") (pinfunction "GND_27") (pintype "passive"))
      (node (ref "U1") (pin "2") (pinfunction "GND_2") (pintype "passive"))
      (node (ref "U2") (pin "1") (pinfunction "A0_1") (pintype "passive"))
      (node (ref "U2") (pin "2") (pinfunction "A1_2") (pintype "passive"))
      (node (ref "U2") (pin "3") (pinfunction "A2_3") (pintype "passive"))
      (node (ref "U2") (pin "4") (pinfunction "GND_4") (pintype "passive"))
      (node (ref "U2") (pin "7") (pinfunction "WP_7") (pintype "passive"))
      (node (ref "U3") (pin "1") (pinfunction "GND_1") (pintype "passive"))
      (node (ref "U4") (pin "1") (pinfunction "GND_1") (pintype "passive"))
      (node (ref "U5") (pin "1") (pinfunction "GND_1") (pintype "passive"))
      (node (ref "U6") (pin "1") (pinfunction "GND_1") (pintype "passive"))
      (node (ref "U7") (pin "4") (pinfunction "GND_4") (pintype "passive"))
      (node (ref "U8") (pin "12") (pinfunction "VSSA_12") (pintype "passive"))
      (node (ref "U8") (pin "47") (pinfunction "VSS_47") (pintype "passive"))
      (node (ref "USB_232") (pin "5") (pinfunction "GND_5") (pintype "passive"))
      (node (ref "VOUT1") (pin "2") (pinfunction "2_2") (pintype "passive"))
      (node (ref "VOUT1") (pin "4") (pinfunction "4_4") (pintype "passive"))
      (node (ref "VOUT1") (pin "6") (pinfunction "6_6") (pintype "passive"))
      (node (ref "VOUT2") (pin "1") (pinfunction "1_1") (pintype "passive"))
      (node (ref "VOUT2") (pin "3") (pinfunction "3_3") (pintype "passive"))
      (node (ref "VOUT2") (pin "5") (pinfunction "5_5") (pintype "passive"))
    )
    (net (code "60") (name "Net-(BAT1-VCC)") (class "Default")
      (node (ref "BAT1") (pin "1") (pinfunction "VCC_1") (pintype "passive"))
      (node (ref "D5") (pin "1") (pintype "passive"))
    )
    (net (code "61") (name "Net-(BOOT-Pad3)") (class "Default")
      (node (ref "BOOT") (pin "3") (pinfunction "3_3") (pintype "passive"))
      (node (ref "R27") (pin "1") (pintype "passive"))
    )
    (net (code "62") (name "Net-(BOOT-Pad4)") (class "Default")
      (node (ref "BOOT") (pin "4") (pinfunction "4_4") (pintype "passive"))
      (node (ref "R28") (pin "2") (pintype "passive"))
    )
    (net (code "63") (name "Net-(C1-VCC)") (class "Default")
      (node (ref "C1") (pin "1") (pinfunction "VCC_1") (pintype "passive"))
      (node (ref "C2") (pin "1") (pintype "passive"))
      (node (ref "K1") (pin "2") (pinfunction "TAP1_2") (pintype "passive"))
      (node (ref "K1") (pin "5") (pinfunction "TAP2_5") (pintype "passive"))
      (node (ref "U4") (pin "3") (pinfunction "IN_3") (pintype "passive"))
      (node (ref "VOUT1") (pin "1") (pinfunction "1_1") (pintype "passive"))
      (node (ref "VOUT1") (pin "3") (pinfunction "3_3") (pintype "passive"))
      (node (ref "VOUT1") (pin "5") (pinfunction "5_5") (pintype "passive"))
    )
    (net (code "64") (name "Net-(C13-Pad2)") (class "Default")
      (node (ref "C13") (pin "2") (pintype "passive"))
      (node (ref "JTAG") (pin "4") (pinfunction "GND_4") (pintype "passive"))
    )
    (net (code "65") (name "Net-(DS0-A)") (class "Default")
      (node (ref "DS0") (pin "1") (pinfunction "A_1") (pintype "passive"))
      (node (ref "R16") (pin "1") (pintype "passive"))
    )
    (net (code "66") (name "Net-(DS1-A)") (class "Default")
      (node (ref "DS1") (pin "1") (pinfunction "A_1") (pintype "passive"))
      (node (ref "R20") (pin "1") (pintype "passive"))
    )
    (net (code "67") (name "Net-(Q1-B)") (class "Default")
      (node (ref "Q1") (pin "2") (pinfunction "B_2") (pintype "passive"))
      (node (ref "R8") (pin "1") (pintype "passive"))
    )
    (net (code "68") (name "Net-(Q1-C)") (class "Default")
      (node (ref "D2") (pin "2") (pintype "passive"))
      (node (ref "Q1") (pin "3") (pinfunction "C_3") (pintype "passive"))
      (node (ref "R2") (pin "2") (pintype "passive"))
    )
    (net (code "69") (name "Net-(Q1-E)") (class "Default")
      (node (ref "Q1") (pin "1") (pinfunction "E_1") (pintype "passive"))
      (node (ref "R11") (pin "2") (pintype "passive"))
      (node (ref "U3") (pin "14") (pinfunction "RTS#_14") (pintype "passive"))
    )
    (net (code "70") (name "Net-(Q2-B)") (class "Default")
      (node (ref "Q2") (pin "2") (pinfunction "B_2") (pintype "passive"))
      (node (ref "R11") (pin "1") (pintype "passive"))
    )
    (net (code "71") (name "Net-(Q2-C)") (class "Default")
      (node (ref "Q2") (pin "3") (pinfunction "C_3") (pintype "passive"))
      (node (ref "R4") (pin "1") (pintype "passive"))
    )
    (net (code "72") (name "Net-(SYS-A)") (class "Default")
      (node (ref "R23") (pin "1") (pintype "passive"))
      (node (ref "SYS") (pin "1") (pinfunction "A_1") (pintype "passive"))
    )
    (net (code "73") (name "Net-(U3-DTR#)") (class "Default")
      (node (ref "R8") (pin "2") (pintype "passive"))
      (node (ref "U3") (pin "13") (pinfunction "DTR#_13") (pintype "passive"))
    )
    (net (code "74") (name "Net-(U3-V3)") (class "Default")
      (node (ref "C9") (pin "2") (pintype "passive"))
      (node (ref "U3") (pin "4") (pinfunction "V3_4") (pintype "passive"))
    )
    (net (code "75") (name "Net-(U3-XI)") (class "Default")
      (node (ref "C11") (pin "2") (pintype "passive"))
      (node (ref "U3") (pin "7") (pinfunction "XI_7") (pintype "passive"))
      (node (ref "Y1") (pin "1") (pinfunction "OSC1_1") (pintype "passive"))
    )
    (net (code "76") (name "Net-(U3-XO)") (class "Default")
      (node (ref "C12") (pin "2") (pintype "passive"))
      (node (ref "U3") (pin "8") (pinfunction "XO_8") (pintype "passive"))
      (node (ref "Y1") (pin "2") (pinfunction "OSC2_2") (pintype "passive"))
    )
    (net (code "77") (name "Net-(U6-IRQ)") (class "Default")
      (node (ref "R15") (pin "1") (pintype "passive"))
      (node (ref "U6") (pin "8") (pinfunction "IRQ_8") (pintype "passive"))
    )
    (net (code "78") (name "Net-(U8-PC14{slash}OSC32)") (class "Default")
      (node (ref "C21") (pin "2") (pintype "passive"))
      (node (ref "U8") (pin "3") (pinfunction "PC14/OSC32_3") (pintype "passive"))
      (node (ref "Y2") (pin "1") (pinfunction "OSC1_1") (pintype "passive"))
    )
    (net (code "79") (name "Net-(U8-PC15{slash}OSC32)") (class "Default")
      (node (ref "C22") (pin "2") (pintype "passive"))
      (node (ref "U8") (pin "4") (pinfunction "PC15/OSC32_4") (pintype "passive"))
      (node (ref "Y2") (pin "2") (pinfunction "OSC2_2") (pintype "passive"))
    )
    (net (code "80") (name "Net-(U8-PD0{slash}OSCIN)") (class "Default")
      (node (ref "C23") (pin "2") (pintype "passive"))
      (node (ref "R26") (pin "2") (pintype "passive"))
      (node (ref "U8") (pin "5") (pinfunction "PD0/OSCIN_5") (pintype "passive"))
      (node (ref "Y3") (pin "1") (pinfunction "OSC1_1") (pintype "passive"))
    )
    (net (code "81") (name "Net-(U8-PD1{slash}OSCOUT)") (class "Default")
      (node (ref "C24") (pin "2") (pintype "passive"))
      (node (ref "R26") (pin "1") (pintype "passive"))
      (node (ref "U8") (pin "6") (pinfunction "PD1/OSCOUT_6") (pintype "passive"))
      (node (ref "Y3") (pin "2") (pinfunction "OSC2_2") (pintype "passive"))
    )
    (net (code "82") (name "Net-(U8-VBAT)") (class "Default")
      (node (ref "D4") (pin "2") (pintype "passive"))
      (node (ref "D5") (pin "2") (pintype "passive"))
      (node (ref "U8") (pin "1") (pinfunction "VBAT_1") (pintype "passive"))
    )
    (net (code "83") (name "Net-(U8-VDDA)") (class "Default")
      (node (ref "C25") (pin "1") (pintype "passive"))
      (node (ref "C26") (pin "1") (pintype "passive"))
      (node (ref "R29") (pin "1") (pintype "passive"))
      (node (ref "U8") (pin "13") (pinfunction "VDDA_13") (pintype "passive"))
    )
    (net (code "84") (name "Net-(USB-GND)") (class "Default")
      (node (ref "F1") (pin "1") (pintype "passive"))
      (node (ref "USB") (pin "5") (pinfunction "GND_5") (pintype "passive"))
    )
    (net (code "85") (name "Net-(USB_232-D+)") (class "Default")
      (node (ref "R13") (pin "2") (pintype "passive"))
      (node (ref "USB_232") (pin "3") (pinfunction "D+_3") (pintype "passive"))
    )
    (net (code "86") (name "Net-(USB_232-D-)") (class "Default")
      (node (ref "R14") (pin "2") (pintype "passive"))
      (node (ref "USB_232") (pin "2") (pinfunction "D-_2") (pintype "passive"))
    )
    (net (code "87") (name "VCC") (class "Default")
      (node (ref "WK_UP") (pin "1") (pinfunction "1_1") (pintype "passive"))
    )
    (net (code "88") (name "VCC3.3") (class "Default")
      (node (ref "BOOT") (pin "1") (pinfunction "1_1") (pintype "passive"))
      (node (ref "BOOT") (pin "2") (pinfunction "2_2") (pintype "passive"))
      (node (ref "C10") (pin "1") (pintype "passive"))
      (node (ref "C13") (pin "1") (pintype "passive"))
      (node (ref "C14") (pin "1") (pintype "passive"))
      (node (ref "C15") (pin "1") (pintype "passive"))
      (node (ref "C17") (pin "2") (pintype "passive"))
      (node (ref "C18") (pin "2") (pintype "passive"))
      (node (ref "C20") (pin "2") (pintype "passive"))
      (node (ref "C27") (pin "2") (pintype "passive"))
      (node (ref "C28") (pin "1") (pintype "passive"))
      (node (ref "C29") (pin "2") (pintype "passive"))
      (node (ref "C3") (pin "2") (pintype "passive"))
      (node (ref "C30") (pin "1") (pintype "passive"))
      (node (ref "C32") (pin "1") (pintype "passive"))
      (node (ref "C6") (pin "1") (pintype "passive"))
      (node (ref "C7") (pin "1") (pinfunction "VCC_1") (pintype "passive"))
      (node (ref "C8") (pin "1") (pintype "passive"))
      (node (ref "D1") (pin "2") (pintype "passive"))
      (node (ref "D4") (pin "1") (pintype "passive"))
      (node (ref "JTAG") (pin "1") (pinfunction "VDD_1") (pintype "passive"))
      (node (ref "JTAG") (pin "2") (pinfunction "VDD_2") (pintype "passive"))
      (node (ref "OLED") (pin "2") (pinfunction "2_2") (pintype "passive"))
      (node (ref "Q2") (pin "1") (pinfunction "E_1") (pintype "passive"))
      (node (ref "R1") (pin "1") (pintype "passive"))
      (node (ref "R10") (pin "2") (pintype "passive"))
      (node (ref "R12") (pin "1") (pintype "passive"))
      (node (ref "R16") (pin "2") (pintype "passive"))
      (node (ref "R17") (pin "2") (pintype "passive"))
      (node (ref "R18") (pin "2") (pintype "passive"))
      (node (ref "R19") (pin "2") (pintype "passive"))
      (node (ref "R2") (pin "1") (pintype "passive"))
      (node (ref "R20") (pin "2") (pintype "passive"))
      (node (ref "R21") (pin "2") (pintype "passive"))
      (node (ref "R22") (pin "2") (pintype "passive"))
      (node (ref "R23") (pin "2") (pintype "passive"))
      (node (ref "R25") (pin "2") (pintype "passive"))
      (node (ref "R29") (pin "2") (pintype "passive"))
      (node (ref "R3") (pin "2") (pintype "passive"))
      (node (ref "R5") (pin "2") (pintype "passive"))
      (node (ref "R6") (pin "2") (pintype "passive"))
      (node (ref "R7") (pin "2") (pintype "passive"))
      (node (ref "R9") (pin "2") (pintype "passive"))
      (node (ref "SD_CARD") (pin "4") (pinfunction "VDD_4") (pintype "passive"))
      (node (ref "TFTLCD") (pin "24") (pinfunction "VDD3.3_24") (pintype "passive"))
      (node (ref "TFTLCD") (pin "25") (pinfunction "VDD3.3_25") (pintype "passive"))
      (node (ref "U1") (pin "3") (pinfunction "VCC_3") (pintype "passive"))
      (node (ref "U2") (pin "8") (pinfunction "VCC1_8") (pintype "passive"))
      (node (ref "U4") (pin "2") (pinfunction "OUT_2") (pintype "passive"))
      (node (ref "U4") (pin "4") (pinfunction "OUT_4") (pintype "passive"))
      (node (ref "U5") (pin "3") (pinfunction "VCC_3") (pintype "passive"))
      (node (ref "U6") (pin "2") (pinfunction "VCC_2") (pintype "passive"))
      (node (ref "U7") (pin "3") (pinfunction "WP#_3") (pintype "passive"))
      (node (ref "U7") (pin "7") (pinfunction "HOLD_7") (pintype "passive"))
      (node (ref "U7") (pin "8") (pinfunction "VCC_8") (pintype "passive"))
      (node (ref "U8") (pin "19") (pinfunction "VDD_19") (pintype "passive"))
      (node (ref "U8") (pin "32") (pinfunction "VDD_32") (pintype "passive"))
      (node (ref "U8") (pin "48") (pinfunction "VDD_48") (pintype "passive"))
      (node (ref "U8") (pin "64") (pinfunction "VDD_64") (pintype "passive"))
      (node (ref "VOUT2") (pin "2") (pinfunction "2_2") (pintype "passive"))
      (node (ref "VOUT2") (pin "4") (pinfunction "4_4") (pintype "passive"))
      (node (ref "VOUT2") (pin "6") (pinfunction "6_6") (pintype "passive"))
    )
    (net (code "89") (name "VCC5") (class "Default")
      (node (ref "C16") (pin "2") (pintype "passive"))
      (node (ref "C31") (pin "2") (pintype "passive"))
      (node (ref "C4") (pin "1") (pintype "passive"))
      (node (ref "C5") (pin "1") (pintype "passive"))
      (node (ref "D3") (pin "2") (pintype "passive"))
      (node (ref "K1") (pin "1") (pinfunction "I/O1_1") (pintype "passive"))
      (node (ref "K1") (pin "6") (pinfunction "I/O2_6") (pintype "passive"))
      (node (ref "PS/2") (pin "4") (pinfunction "VCC_4") (pintype "passive"))
      (node (ref "TFTLCD") (pin "28") (pinfunction "BL_VDD_28") (pintype "passive"))
      (node (ref "U3") (pin "16") (pinfunction "VCC_16") (pintype "passive"))
      (node (ref "USB") (pin "1") (pinfunction "VCC_1") (pintype "passive"))
      (node (ref "USB_232") (pin "1") (pinfunction "VCC_1") (pintype "passive"))
    )
    (net (code "90") (name "unconnected-(JTAG-NC-Pad11)") (class "Default")
      (node (ref "JTAG") (pin "11") (pinfunction "NC_11") (pintype "passive+no_connect"))
    )
    (net (code "91") (name "unconnected-(JTAG-NC-Pad17)") (class "Default")
      (node (ref "JTAG") (pin "17") (pinfunction "NC_17") (pintype "passive+no_connect"))
    )
    (net (code "92") (name "unconnected-(JTAG-NC-Pad19)") (class "Default")
      (node (ref "JTAG") (pin "19") (pinfunction "NC_19") (pintype "passive+no_connect"))
    )
    (net (code "93") (name "unconnected-(K1-I{slash}O1-Pad3)") (class "Default")
      (node (ref "K1") (pin "3") (pinfunction "I/O1_3") (pintype "passive+no_connect"))
    )
    (net (code "94") (name "unconnected-(K1-I{slash}O2-Pad4)") (class "Default")
      (node (ref "K1") (pin "4") (pinfunction "I/O2_4") (pintype "passive+no_connect"))
    )
    (net (code "95") (name "unconnected-(PS/2-NC-Pad2)") (class "Default")
      (node (ref "PS/2") (pin "2") (pinfunction "NC_2") (pintype "passive"))
    )
    (net (code "96") (name "unconnected-(PS/2-NC-Pad6)") (class "Default")
      (node (ref "PS/2") (pin "6") (pinfunction "NC_6") (pintype "passive"))
    )
    (net (code "97") (name "unconnected-(PS/2-RES-PadS)") (class "Default")
      (node (ref "PS/2") (pin "S") (pinfunction "RES_S") (pintype "passive"))
    )
    (net (code "98") (name "unconnected-(SD_CARD-CD-Pad10)") (class "Default")
      (node (ref "SD_CARD") (pin "10") (pinfunction "CD_10") (pintype "passive+no_connect"))
    )
    (net (code "99") (name "unconnected-(SD_CARD-DATA1-Pad8)") (class "Default")
      (node (ref "SD_CARD") (pin "8") (pinfunction "DATA1_8") (pintype "passive+no_connect"))
    )
    (net (code "100") (name "unconnected-(SD_CARD-DATA2-Pad9)") (class "Default")
      (node (ref "SD_CARD") (pin "9") (pinfunction "DATA2_9") (pintype "passive+no_connect"))
    )
    (net (code "101") (name "unconnected-(SD_CARD-GND-Pad11)") (class "Default")
      (node (ref "SD_CARD") (pin "11") (pinfunction "GND_11") (pintype "passive+no_connect"))
    )
    (net (code "102") (name "unconnected-(SD_CARD-WP-Pad12)") (class "Default")
      (node (ref "SD_CARD") (pin "12") (pinfunction "WP_12") (pintype "passive+no_connect"))
    )
    (net (code "103") (name "unconnected-(TFTLCD-MO-Pad32)") (class "Default")
      (node (ref "TFTLCD") (pin "32") (pinfunction "MO_32") (pintype "passive+no_connect"))
    )
    (net (code "104") (name "unconnected-(U3-CTS#-Pad9)") (class "Default")
      (node (ref "U3") (pin "9") (pinfunction "CTS#_9") (pintype "passive+no_connect"))
    )
    (net (code "105") (name "unconnected-(U3-DCD#-Pad12)") (class "Default")
      (node (ref "U3") (pin "12") (pinfunction "DCD#_12") (pintype "passive+no_connect"))
    )
    (net (code "106") (name "unconnected-(U3-DSR#-Pad10)") (class "Default")
      (node (ref "U3") (pin "10") (pinfunction "DSR#_10") (pintype "passive+no_connect"))
    )
    (net (code "107") (name "unconnected-(U3-R232-Pad15)") (class "Default")
      (node (ref "U3") (pin "15") (pinfunction "R232_15") (pintype "passive+no_connect"))
    )
    (net (code "108") (name "unconnected-(U3-RI#-Pad11)") (class "Default")
      (node (ref "U3") (pin "11") (pinfunction "RI#_11") (pintype "passive+no_connect"))
    )
    (net (code "109") (name "unconnected-(USB-NC-Pad4)") (class "Default")
      (node (ref "USB") (pin "4") (pinfunction "NC_4") (pintype "passive+no_connect"))
    )
    (net (code "110") (name "unconnected-(USB_232-NC-Pad4)") (class "Default")
      (node (ref "USB_232") (pin "4") (pinfunction "NC_4") (pintype "passive"))
    )
  )
)
